# Elektriskeem.net
KiCad netlist of a schematic drawn in EAGLE
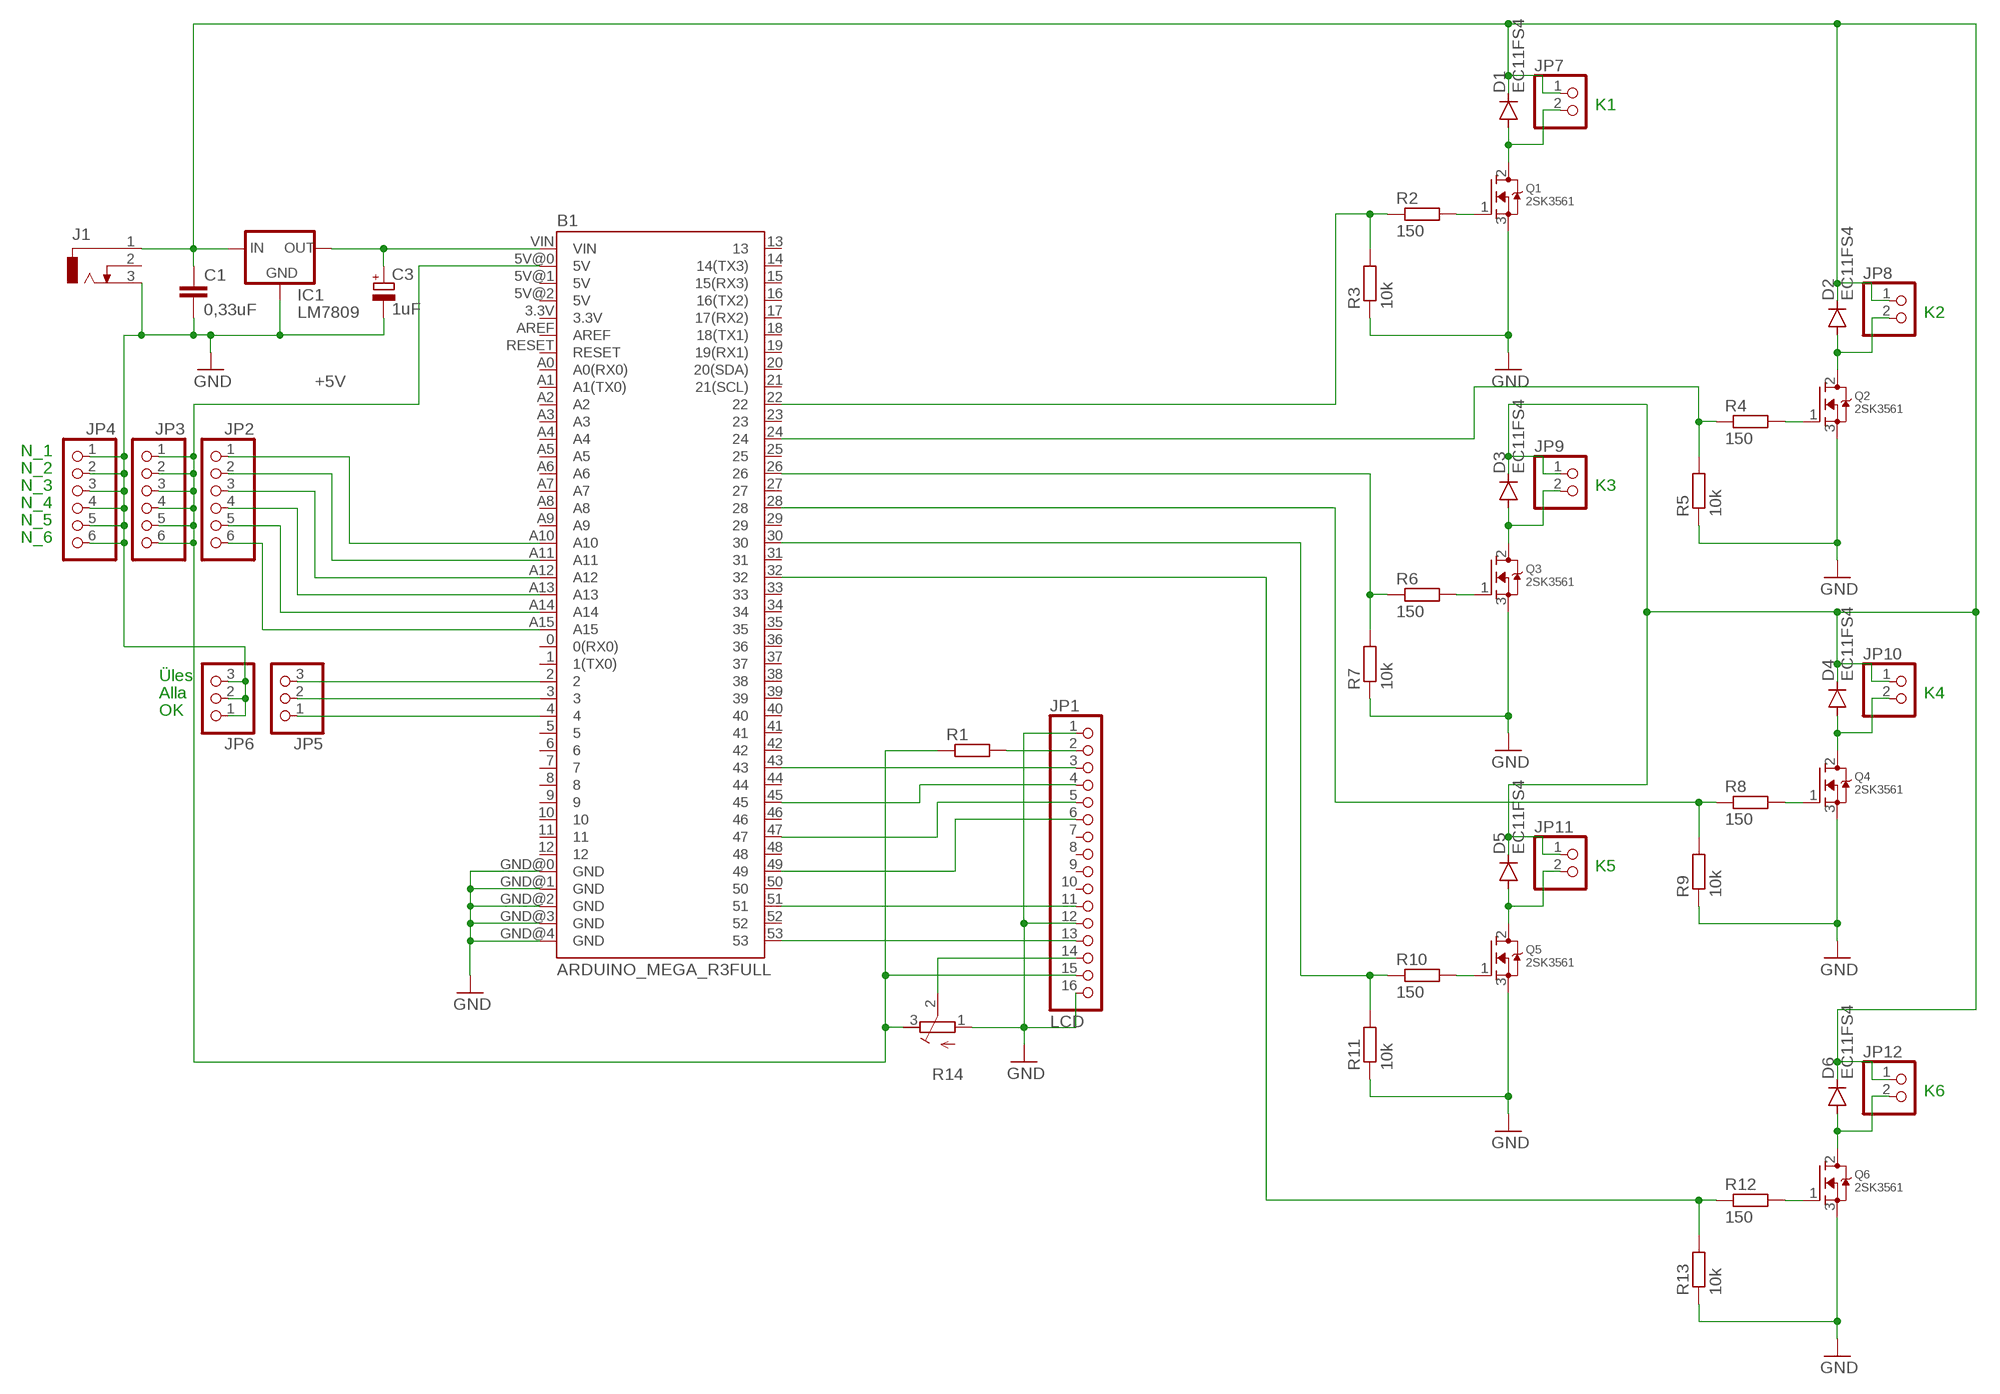
[diagram p0: schematic, sheet 1]

(export (version "E")
  (design (tool "Eeschema 10.0.6"))
  (components
    (comp (ref "B1")
      (value "ARDUINO_MEGA_R3FULL")
      (footprint "eagle-import:ARDUINO_MEGA")
      (libsource (lib "eagle-import") (part "ARDUINO_MEGA_R3FULL"))
    )
    (comp (ref "C1")
      (value "0,33uF")
      (footprint "eagle-import:C102-043X133")
      (libsource (lib "eagle-import") (part "C-EU102-043X133"))
    )
    (comp (ref "C3")
      (value "1uF")
      (footprint "eagle-import:E2,5-6")
      (libsource (lib "eagle-import") (part "CPOL-EUE2.5-6"))
    )
    (comp (ref "D1")
      (value "EC11FS4")
      (footprint "eagle-import:DO214AA")
      (libsource (lib "eagle-import") (part "DIODE-DO214AA"))
    )
    (comp (ref "D2")
      (value "EC11FS4")
      (footprint "eagle-import:DO214AA")
      (libsource (lib "eagle-import") (part "DIODE-DO214AA"))
    )
    (comp (ref "D3")
      (value "EC11FS4")
      (footprint "eagle-import:DO214AA")
      (libsource (lib "eagle-import") (part "DIODE-DO214AA"))
    )
    (comp (ref "D4")
      (value "EC11FS4")
      (footprint "eagle-import:DO214AA")
      (libsource (lib "eagle-import") (part "DIODE-DO214AA"))
    )
    (comp (ref "D5")
      (value "EC11FS4")
      (footprint "eagle-import:DO214AA")
      (libsource (lib "eagle-import") (part "DIODE-DO214AA"))
    )
    (comp (ref "D6")
      (value "EC11FS4")
      (footprint "eagle-import:DO214AA")
      (libsource (lib "eagle-import") (part "DIODE-DO214AA"))
    )
    (comp (ref "IC1")
      (value "LM7809")
      (footprint "eagle-import:78XXS")
      (libsource (lib "eagle-import") (part "78XXS"))
    )
    (comp (ref "J1")
      (value "DCJ0303")
      (footprint "eagle-import:DCJ0303")
      (libsource (lib "eagle-import") (part "DCJ0303"))
    )
    (comp (ref "JP1")
      (value "LCD")
      (footprint "eagle-import:1X16")
      (libsource (lib "eagle-import") (part "PINHD-1X16"))
    )
    (comp (ref "JP2")
      (value "PINHD-1X6")
      (footprint "eagle-import:1X06")
      (libsource (lib "eagle-import") (part "PINHD-1X6"))
    )
    (comp (ref "JP3")
      (value "PINHD-1X6")
      (footprint "eagle-import:1X06")
      (libsource (lib "eagle-import") (part "PINHD-1X6"))
    )
    (comp (ref "JP4")
      (value "PINHD-1X6")
      (footprint "eagle-import:1X06")
      (libsource (lib "eagle-import") (part "PINHD-1X6"))
    )
    (comp (ref "JP5")
      (value "PINHD-1X3")
      (footprint "eagle-import:1X03")
      (libsource (lib "eagle-import") (part "PINHD-1X3"))
    )
    (comp (ref "JP6")
      (value "PINHD-1X3")
      (footprint "eagle-import:1X03")
      (libsource (lib "eagle-import") (part "PINHD-1X3"))
    )
    (comp (ref "JP7")
      (value "PINHD-1X2")
      (footprint "eagle-import:1X02")
      (libsource (lib "eagle-import") (part "PINHD-1X2"))
    )
    (comp (ref "JP8")
      (value "PINHD-1X2")
      (footprint "eagle-import:1X02")
      (libsource (lib "eagle-import") (part "PINHD-1X2"))
    )
    (comp (ref "JP9")
      (value "PINHD-1X2")
      (footprint "eagle-import:1X02")
      (libsource (lib "eagle-import") (part "PINHD-1X2"))
    )
    (comp (ref "JP10")
      (value "PINHD-1X2")
      (footprint "eagle-import:1X02")
      (libsource (lib "eagle-import") (part "PINHD-1X2"))
    )
    (comp (ref "JP11")
      (value "PINHD-1X2")
      (footprint "eagle-import:1X02")
      (libsource (lib "eagle-import") (part "PINHD-1X2"))
    )
    (comp (ref "JP12")
      (value "PINHD-1X2")
      (footprint "eagle-import:1X02")
      (libsource (lib "eagle-import") (part "PINHD-1X2"))
    )
    (comp (ref "Q1")
      (value "2SK3561")
      (footprint "eagle-import:TO220V")
      (libsource (lib "eagle-import") (part "MOSFET-NGDS_TO220V"))
    )
    (comp (ref "Q2")
      (value "2SK3561")
      (footprint "eagle-import:TO220V")
      (libsource (lib "eagle-import") (part "MOSFET-NGDS_TO220V"))
    )
    (comp (ref "Q3")
      (value "2SK3561")
      (footprint "eagle-import:TO220V")
      (libsource (lib "eagle-import") (part "MOSFET-NGDS_TO220V"))
    )
    (comp (ref "Q4")
      (value "2SK3561")
      (footprint "eagle-import:TO220V")
      (libsource (lib "eagle-import") (part "MOSFET-NGDS_TO220V"))
    )
    (comp (ref "Q5")
      (value "2SK3561")
      (footprint "eagle-import:TO220V")
      (libsource (lib "eagle-import") (part "MOSFET-NGDS_TO220V"))
    )
    (comp (ref "Q6")
      (value "2SK3561")
      (footprint "eagle-import:TO220V")
      (libsource (lib "eagle-import") (part "MOSFET-NGDS_TO220V"))
    )
    (comp (ref "R1")
      (value "R-EU_0207/12")
      (footprint "eagle-import:0207_12")
      (libsource (lib "eagle-import") (part "R-EU_0207/12"))
    )
    (comp (ref "R2")
      (value "150")
      (footprint "eagle-import:0207_12")
      (libsource (lib "eagle-import") (part "R-EU_0207/12"))
    )
    (comp (ref "R3")
      (value "10k")
      (footprint "eagle-import:0207_12")
      (libsource (lib "eagle-import") (part "R-EU_0207/12"))
    )
    (comp (ref "R4")
      (value "150")
      (footprint "eagle-import:0207_12")
      (libsource (lib "eagle-import") (part "R-EU_0207/12"))
    )
    (comp (ref "R5")
      (value "10k")
      (footprint "eagle-import:0207_12")
      (libsource (lib "eagle-import") (part "R-EU_0207/12"))
    )
    (comp (ref "R6")
      (value "150")
      (footprint "eagle-import:0207_12")
      (libsource (lib "eagle-import") (part "R-EU_0207/12"))
    )
    (comp (ref "R7")
      (value "10k")
      (footprint "eagle-import:0207_12")
      (libsource (lib "eagle-import") (part "R-EU_0207/12"))
    )
    (comp (ref "R8")
      (value "150")
      (footprint "eagle-import:0207_12")
      (libsource (lib "eagle-import") (part "R-EU_0207/12"))
    )
    (comp (ref "R9")
      (value "10k")
      (footprint "eagle-import:0207_12")
      (libsource (lib "eagle-import") (part "R-EU_0207/12"))
    )
    (comp (ref "R10")
      (value "150")
      (footprint "eagle-import:0207_12")
      (libsource (lib "eagle-import") (part "R-EU_0207/12"))
    )
    (comp (ref "R11")
      (value "10k")
      (footprint "eagle-import:0207_12")
      (libsource (lib "eagle-import") (part "R-EU_0207/12"))
    )
    (comp (ref "R12")
      (value "150")
      (footprint "eagle-import:0207_12")
      (libsource (lib "eagle-import") (part "R-EU_0207/12"))
    )
    (comp (ref "R13")
      (value "10k")
      (footprint "eagle-import:0207_12")
      (libsource (lib "eagle-import") (part "R-EU_0207/12"))
    )
    (comp (ref "R14")
      (value "R-TRIMM3339P")
      (footprint "eagle-import:RTRIM3339P")
      (libsource (lib "eagle-import") (part "R-TRIMM3339P"))
    )
  )
  (nets
    (net (code "1") (name "/+5V") (class "Default")
      (node (ref "B1") (pin "5V@0") (pinfunction "5V_5V@0") (pintype "bidirectional"))
      (node (ref "JP1") (pin "15") (pinfunction "15_15") (pintype "passive"))
      (node (ref "JP3") (pin "1") (pinfunction "1_1") (pintype "passive"))
      (node (ref "JP3") (pin "2") (pinfunction "2_2") (pintype "passive"))
      (node (ref "JP3") (pin "3") (pinfunction "3_3") (pintype "passive"))
      (node (ref "JP3") (pin "4") (pinfunction "4_4") (pintype "passive"))
      (node (ref "JP3") (pin "5") (pinfunction "5_5") (pintype "passive"))
      (node (ref "JP3") (pin "6") (pinfunction "6_6") (pintype "passive"))
      (node (ref "R1") (pin "1") (pinfunction "1_1") (pintype "passive"))
      (node (ref "R14") (pin "3") (pinfunction "E_3") (pintype "passive"))
    )
    (net (code "2") (name "GND") (class "Default")
      (node (ref "B1") (pin "GND@0") (pinfunction "GND_GND@0") (pintype "bidirectional"))
      (node (ref "B1") (pin "GND@1") (pinfunction "GND_GND@1") (pintype "bidirectional"))
      (node (ref "B1") (pin "GND@2") (pinfunction "GND_GND@2") (pintype "bidirectional"))
      (node (ref "B1") (pin "GND@3") (pinfunction "GND_GND@3") (pintype "bidirectional"))
      (node (ref "B1") (pin "GND@4") (pinfunction "GND_GND@4") (pintype "bidirectional"))
      (node (ref "C1") (pin "2") (pinfunction "2_2") (pintype "passive"))
      (node (ref "C3") (pin "-") (pinfunction "-_-") (pintype "passive"))
      (node (ref "IC1") (pin "GND") (pinfunction "GND_GND") (pintype "input"))
      (node (ref "J1") (pin "3") (pinfunction "3_3") (pintype "passive"))
      (node (ref "JP1") (pin "1") (pinfunction "1_1") (pintype "passive"))
      (node (ref "JP1") (pin "12") (pinfunction "12_12") (pintype "passive"))
      (node (ref "JP1") (pin "16") (pinfunction "16_16") (pintype "passive"))
      (node (ref "JP4") (pin "1") (pinfunction "1_1") (pintype "passive"))
      (node (ref "JP4") (pin "2") (pinfunction "2_2") (pintype "passive"))
      (node (ref "JP4") (pin "3") (pinfunction "3_3") (pintype "passive"))
      (node (ref "JP4") (pin "4") (pinfunction "4_4") (pintype "passive"))
      (node (ref "JP4") (pin "5") (pinfunction "5_5") (pintype "passive"))
      (node (ref "JP4") (pin "6") (pinfunction "6_6") (pintype "passive"))
      (node (ref "JP6") (pin "1") (pinfunction "1_1") (pintype "passive"))
      (node (ref "JP6") (pin "2") (pinfunction "2_2") (pintype "passive"))
      (node (ref "JP6") (pin "3") (pinfunction "3_3") (pintype "passive"))
      (node (ref "Q1") (pin "3") (pinfunction "S_3") (pintype "bidirectional"))
      (node (ref "Q2") (pin "3") (pinfunction "S_3") (pintype "bidirectional"))
      (node (ref "Q3") (pin "3") (pinfunction "S_3") (pintype "bidirectional"))
      (node (ref "Q4") (pin "3") (pinfunction "S_3") (pintype "bidirectional"))
      (node (ref "Q5") (pin "3") (pinfunction "S_3") (pintype "bidirectional"))
      (node (ref "Q6") (pin "3") (pinfunction "S_3") (pintype "bidirectional"))
      (node (ref "R11") (pin "1") (pinfunction "1_1") (pintype "passive"))
      (node (ref "R13") (pin "1") (pinfunction "1_1") (pintype "passive"))
      (node (ref "R14") (pin "1") (pinfunction "A_1") (pintype "passive"))
      (node (ref "R3") (pin "1") (pinfunction "1_1") (pintype "passive"))
      (node (ref "R5") (pin "1") (pinfunction "1_1") (pintype "passive"))
      (node (ref "R7") (pin "1") (pinfunction "1_1") (pintype "passive"))
      (node (ref "R9") (pin "1") (pinfunction "1_1") (pintype "passive"))
    )
    (net (code "3") (name "Net-(B1-Pad2)") (class "Default")
      (node (ref "B1") (pin "2") (pinfunction "2_2") (pintype "bidirectional"))
      (node (ref "JP5") (pin "3") (pinfunction "3_3") (pintype "passive"))
    )
    (net (code "4") (name "Net-(B1-Pad3)") (class "Default")
      (node (ref "B1") (pin "3") (pinfunction "3_3") (pintype "bidirectional"))
      (node (ref "JP5") (pin "2") (pinfunction "2_2") (pintype "passive"))
    )
    (net (code "5") (name "Net-(B1-Pad4)") (class "Default")
      (node (ref "B1") (pin "4") (pinfunction "4_4") (pintype "bidirectional"))
      (node (ref "JP5") (pin "1") (pinfunction "1_1") (pintype "passive"))
    )
    (net (code "6") (name "Net-(B1-Pad22)") (class "Default")
      (node (ref "B1") (pin "22") (pinfunction "22_22") (pintype "bidirectional"))
      (node (ref "R2") (pin "1") (pinfunction "1_1") (pintype "passive"))
      (node (ref "R3") (pin "2") (pinfunction "2_2") (pintype "passive"))
    )
    (net (code "7") (name "Net-(B1-Pad24)") (class "Default")
      (node (ref "B1") (pin "24") (pinfunction "24_24") (pintype "bidirectional"))
      (node (ref "R4") (pin "1") (pinfunction "1_1") (pintype "passive"))
      (node (ref "R5") (pin "2") (pinfunction "2_2") (pintype "passive"))
    )
    (net (code "8") (name "Net-(B1-Pad26)") (class "Default")
      (node (ref "B1") (pin "26") (pinfunction "26_26") (pintype "bidirectional"))
      (node (ref "R6") (pin "1") (pinfunction "1_1") (pintype "passive"))
      (node (ref "R7") (pin "2") (pinfunction "2_2") (pintype "passive"))
    )
    (net (code "9") (name "Net-(B1-Pad28)") (class "Default")
      (node (ref "B1") (pin "28") (pinfunction "28_28") (pintype "bidirectional"))
      (node (ref "R8") (pin "1") (pinfunction "1_1") (pintype "passive"))
      (node (ref "R9") (pin "2") (pinfunction "2_2") (pintype "passive"))
    )
    (net (code "10") (name "Net-(B1-Pad30)") (class "Default")
      (node (ref "B1") (pin "30") (pinfunction "30_30") (pintype "bidirectional"))
      (node (ref "R10") (pin "1") (pinfunction "1_1") (pintype "passive"))
      (node (ref "R11") (pin "2") (pinfunction "2_2") (pintype "passive"))
    )
    (net (code "11") (name "Net-(B1-Pad32)") (class "Default")
      (node (ref "B1") (pin "32") (pinfunction "32_32") (pintype "bidirectional"))
      (node (ref "R12") (pin "1") (pinfunction "1_1") (pintype "passive"))
      (node (ref "R13") (pin "2") (pinfunction "2_2") (pintype "passive"))
    )
    (net (code "12") (name "Net-(B1-Pad43)") (class "Default")
      (node (ref "B1") (pin "43") (pinfunction "43_43") (pintype "bidirectional"))
      (node (ref "JP1") (pin "3") (pinfunction "3_3") (pintype "passive"))
    )
    (net (code "13") (name "Net-(B1-Pad45)") (class "Default")
      (node (ref "B1") (pin "45") (pinfunction "45_45") (pintype "bidirectional"))
      (node (ref "JP1") (pin "4") (pinfunction "4_4") (pintype "passive"))
    )
    (net (code "14") (name "Net-(B1-Pad47)") (class "Default")
      (node (ref "B1") (pin "47") (pinfunction "47_47") (pintype "bidirectional"))
      (node (ref "JP1") (pin "5") (pinfunction "5_5") (pintype "passive"))
    )
    (net (code "15") (name "Net-(B1-Pad49)") (class "Default")
      (node (ref "B1") (pin "49") (pinfunction "49_49") (pintype "bidirectional"))
      (node (ref "JP1") (pin "6") (pinfunction "6_6") (pintype "passive"))
    )
    (net (code "16") (name "Net-(B1-Pad51)") (class "Default")
      (node (ref "B1") (pin "51") (pinfunction "51_51") (pintype "bidirectional"))
      (node (ref "JP1") (pin "11") (pinfunction "11_11") (pintype "passive"))
    )
    (net (code "17") (name "Net-(B1-Pad53)") (class "Default")
      (node (ref "B1") (pin "53") (pinfunction "53_53") (pintype "bidirectional"))
      (node (ref "JP1") (pin "13") (pinfunction "13_13") (pintype "passive"))
    )
    (net (code "18") (name "Net-(B1-PadA10)") (class "Default")
      (node (ref "B1") (pin "A10") (pinfunction "A10_A10") (pintype "bidirectional"))
      (node (ref "JP2") (pin "1") (pinfunction "1_1") (pintype "passive"))
    )
    (net (code "19") (name "Net-(B1-PadA11)") (class "Default")
      (node (ref "B1") (pin "A11") (pinfunction "A11_A11") (pintype "bidirectional"))
      (node (ref "JP2") (pin "2") (pinfunction "2_2") (pintype "passive"))
    )
    (net (code "20") (name "Net-(B1-PadA12)") (class "Default")
      (node (ref "B1") (pin "A12") (pinfunction "A12_A12") (pintype "bidirectional"))
      (node (ref "JP2") (pin "3") (pinfunction "3_3") (pintype "passive"))
    )
    (net (code "21") (name "Net-(B1-PadA13)") (class "Default")
      (node (ref "B1") (pin "A13") (pinfunction "A13_A13") (pintype "bidirectional"))
      (node (ref "JP2") (pin "4") (pinfunction "4_4") (pintype "passive"))
    )
    (net (code "22") (name "Net-(B1-PadA14)") (class "Default")
      (node (ref "B1") (pin "A14") (pinfunction "A14_A14") (pintype "bidirectional"))
      (node (ref "JP2") (pin "5") (pinfunction "5_5") (pintype "passive"))
    )
    (net (code "23") (name "Net-(B1-PadA15)") (class "Default")
      (node (ref "B1") (pin "A15") (pinfunction "A15_A15") (pintype "bidirectional"))
      (node (ref "JP2") (pin "6") (pinfunction "6_6") (pintype "passive"))
    )
    (net (code "24") (name "Net-(B1-PadVIN)") (class "Default")
      (node (ref "B1") (pin "VIN") (pinfunction "VIN_VIN") (pintype "bidirectional"))
      (node (ref "C3") (pin "+") (pinfunction "+_+") (pintype "passive"))
      (node (ref "IC1") (pin "OUT") (pinfunction "OUT_OUT") (pintype "passive"))
    )
    (net (code "25") (name "Net-(C1-Pad1)") (class "Default")
      (node (ref "C1") (pin "1") (pinfunction "1_1") (pintype "passive"))
      (node (ref "D1") (pin "C") (pinfunction "C_C") (pintype "passive"))
      (node (ref "D2") (pin "C") (pinfunction "C_C") (pintype "passive"))
      (node (ref "D3") (pin "C") (pinfunction "C_C") (pintype "passive"))
      (node (ref "D4") (pin "C") (pinfunction "C_C") (pintype "passive"))
      (node (ref "D5") (pin "C") (pinfunction "C_C") (pintype "passive"))
      (node (ref "D6") (pin "C") (pinfunction "C_C") (pintype "passive"))
      (node (ref "IC1") (pin "IN") (pinfunction "IN_IN") (pintype "input"))
      (node (ref "J1") (pin "1") (pinfunction "1_1") (pintype "passive"))
      (node (ref "JP10") (pin "1") (pinfunction "1_1") (pintype "passive"))
      (node (ref "JP11") (pin "1") (pinfunction "1_1") (pintype "passive"))
      (node (ref "JP12") (pin "1") (pinfunction "1_1") (pintype "passive"))
      (node (ref "JP7") (pin "1") (pinfunction "1_1") (pintype "passive"))
      (node (ref "JP8") (pin "1") (pinfunction "1_1") (pintype "passive"))
      (node (ref "JP9") (pin "1") (pinfunction "1_1") (pintype "passive"))
    )
    (net (code "26") (name "Net-(JP1-Pad2)") (class "Default")
      (node (ref "JP1") (pin "2") (pinfunction "2_2") (pintype "passive"))
      (node (ref "R1") (pin "2") (pinfunction "2_2") (pintype "passive"))
    )
    (net (code "27") (name "Net-(Q1-D)") (class "Default")
      (node (ref "D1") (pin "A") (pinfunction "A_A") (pintype "passive"))
      (node (ref "JP7") (pin "2") (pinfunction "2_2") (pintype "passive"))
      (node (ref "Q1") (pin "2") (pinfunction "D_2") (pintype "bidirectional"))
    )
    (net (code "28") (name "Net-(Q1-G)") (class "Default")
      (node (ref "Q1") (pin "1") (pinfunction "G_1") (pintype "bidirectional"))
      (node (ref "R2") (pin "2") (pinfunction "2_2") (pintype "passive"))
    )
    (net (code "29") (name "Net-(Q2-D)") (class "Default")
      (node (ref "D2") (pin "A") (pinfunction "A_A") (pintype "passive"))
      (node (ref "JP8") (pin "2") (pinfunction "2_2") (pintype "passive"))
      (node (ref "Q2") (pin "2") (pinfunction "D_2") (pintype "bidirectional"))
    )
    (net (code "30") (name "Net-(Q2-G)") (class "Default")
      (node (ref "Q2") (pin "1") (pinfunction "G_1") (pintype "bidirectional"))
      (node (ref "R4") (pin "2") (pinfunction "2_2") (pintype "passive"))
    )
    (net (code "31") (name "Net-(Q3-D)") (class "Default")
      (node (ref "D3") (pin "A") (pinfunction "A_A") (pintype "passive"))
      (node (ref "JP9") (pin "2") (pinfunction "2_2") (pintype "passive"))
      (node (ref "Q3") (pin "2") (pinfunction "D_2") (pintype "bidirectional"))
    )
    (net (code "32") (name "Net-(Q3-G)") (class "Default")
      (node (ref "Q3") (pin "1") (pinfunction "G_1") (pintype "bidirectional"))
      (node (ref "R6") (pin "2") (pinfunction "2_2") (pintype "passive"))
    )
    (net (code "33") (name "Net-(Q4-D)") (class "Default")
      (node (ref "D4") (pin "A") (pinfunction "A_A") (pintype "passive"))
      (node (ref "JP10") (pin "2") (pinfunction "2_2") (pintype "passive"))
      (node (ref "Q4") (pin "2") (pinfunction "D_2") (pintype "bidirectional"))
    )
    (net (code "34") (name "Net-(Q4-G)") (class "Default")
      (node (ref "Q4") (pin "1") (pinfunction "G_1") (pintype "bidirectional"))
      (node (ref "R8") (pin "2") (pinfunction "2_2") (pintype "passive"))
    )
    (net (code "35") (name "Net-(Q5-D)") (class "Default")
      (node (ref "D5") (pin "A") (pinfunction "A_A") (pintype "passive"))
      (node (ref "JP11") (pin "2") (pinfunction "2_2") (pintype "passive"))
      (node (ref "Q5") (pin "2") (pinfunction "D_2") (pintype "bidirectional"))
    )
    (net (code "36") (name "Net-(Q5-G)") (class "Default")
      (node (ref "Q5") (pin "1") (pinfunction "G_1") (pintype "bidirectional"))
      (node (ref "R10") (pin "2") (pinfunction "2_2") (pintype "passive"))
    )
    (net (code "37") (name "Net-(Q6-D)") (class "Default")
      (node (ref "D6") (pin "A") (pinfunction "A_A") (pintype "passive"))
      (node (ref "JP12") (pin "2") (pinfunction "2_2") (pintype "passive"))
      (node (ref "Q6") (pin "2") (pinfunction "D_2") (pintype "bidirectional"))
    )
    (net (code "38") (name "Net-(Q6-G)") (class "Default")
      (node (ref "Q6") (pin "1") (pinfunction "G_1") (pintype "bidirectional"))
      (node (ref "R12") (pin "2") (pinfunction "2_2") (pintype "passive"))
    )
    (net (code "39") (name "Net-(R14-S)") (class "Default")
      (node (ref "JP1") (pin "14") (pinfunction "14_14") (pintype "passive"))
      (node (ref "R14") (pin "2") (pinfunction "S_2") (pintype "passive"))
    )
    (net (code "40") (name "unconnected-(B1-0(RX0)-Pad0)") (class "Default")
      (node (ref "B1") (pin "0") (pinfunction "0(RX0)_0") (pintype "bidirectional"))
    )
    (net (code "41") (name "unconnected-(B1-1(TX0)-Pad1)") (class "Default")
      (node (ref "B1") (pin "1") (pinfunction "1(TX0)_1") (pintype "bidirectional"))
    )
    (net (code "42") (name "unconnected-(B1-5V-Pad5V@1)") (class "Default")
      (node (ref "B1") (pin "5V@1") (pinfunction "5V_5V@1") (pintype "bidirectional"))
    )
    (net (code "43") (name "unconnected-(B1-5V-Pad5V@2)") (class "Default")
      (node (ref "B1") (pin "5V@2") (pinfunction "5V_5V@2") (pintype "bidirectional"))
    )
    (net (code "44") (name "unconnected-(B1-14(TX3)-Pad14)") (class "Default")
      (node (ref "B1") (pin "14") (pinfunction "14(TX3)_14") (pintype "bidirectional"))
    )
    (net (code "45") (name "unconnected-(B1-15(RX3)-Pad15)") (class "Default")
      (node (ref "B1") (pin "15") (pinfunction "15(RX3)_15") (pintype "bidirectional"))
    )
    (net (code "46") (name "unconnected-(B1-16(TX2)-Pad16)") (class "Default")
      (node (ref "B1") (pin "16") (pinfunction "16(TX2)_16") (pintype "bidirectional"))
    )
    (net (code "47") (name "unconnected-(B1-17(RX2)-Pad17)") (class "Default")
      (node (ref "B1") (pin "17") (pinfunction "17(RX2)_17") (pintype "bidirectional"))
    )
    (net (code "48") (name "unconnected-(B1-18(TX1)-Pad18)") (class "Default")
      (node (ref "B1") (pin "18") (pinfunction "18(TX1)_18") (pintype "bidirectional"))
    )
    (net (code "49") (name "unconnected-(B1-19(RX1)-Pad19)") (class "Default")
      (node (ref "B1") (pin "19") (pinfunction "19(RX1)_19") (pintype "bidirectional"))
    )
    (net (code "50") (name "unconnected-(B1-20(SDA)-Pad20)") (class "Default")
      (node (ref "B1") (pin "20") (pinfunction "20(SDA)_20") (pintype "bidirectional"))
    )
    (net (code "51") (name "unconnected-(B1-21(SCL)-Pad21)") (class "Default")
      (node (ref "B1") (pin "21") (pinfunction "21(SCL)_21") (pintype "bidirectional"))
    )
    (net (code "52") (name "unconnected-(B1-A0(RX0)-PadA0)") (class "Default")
      (node (ref "B1") (pin "A0") (pinfunction "A0(RX0)_A0") (pintype "bidirectional"))
    )
    (net (code "53") (name "unconnected-(B1-A1(TX0)-PadA1)") (class "Default")
      (node (ref "B1") (pin "A1") (pinfunction "A1(TX0)_A1") (pintype "bidirectional"))
    )
    (net (code "54") (name "unconnected-(B1-Pad3.3V)") (class "Default")
      (node (ref "B1") (pin "3.3V") (pinfunction "3.3V_3.3V") (pintype "bidirectional"))
    )
    (net (code "55") (name "unconnected-(B1-Pad5)") (class "Default")
      (node (ref "B1") (pin "5") (pinfunction "5_5") (pintype "bidirectional"))
    )
    (net (code "56") (name "unconnected-(B1-Pad6)") (class "Default")
      (node (ref "B1") (pin "6") (pinfunction "6_6") (pintype "bidirectional"))
    )
    (net (code "57") (name "unconnected-(B1-Pad7)") (class "Default")
      (node (ref "B1") (pin "7") (pinfunction "7_7") (pintype "bidirectional"))
    )
    (net (code "58") (name "unconnected-(B1-Pad8)") (class "Default")
      (node (ref "B1") (pin "8") (pinfunction "8_8") (pintype "bidirectional"))
    )
    (net (code "59") (name "unconnected-(B1-Pad9)") (class "Default")
      (node (ref "B1") (pin "9") (pinfunction "9_9") (pintype "bidirectional"))
    )
    (net (code "60") (name "unconnected-(B1-Pad10)") (class "Default")
      (node (ref "B1") (pin "10") (pinfunction "10_10") (pintype "bidirectional"))
    )
    (net (code "61") (name "unconnected-(B1-Pad11)") (class "Default")
      (node (ref "B1") (pin "11") (pinfunction "11_11") (pintype "bidirectional"))
    )
    (net (code "62") (name "unconnected-(B1-Pad12)") (class "Default")
      (node (ref "B1") (pin "12") (pinfunction "12_12") (pintype "bidirectional"))
    )
    (net (code "63") (name "unconnected-(B1-Pad13)") (class "Default")
      (node (ref "B1") (pin "13") (pinfunction "13_13") (pintype "bidirectional"))
    )
    (net (code "64") (name "unconnected-(B1-Pad23)") (class "Default")
      (node (ref "B1") (pin "23") (pinfunction "23_23") (pintype "bidirectional"))
    )
    (net (code "65") (name "unconnected-(B1-Pad25)") (class "Default")
      (node (ref "B1") (pin "25") (pinfunction "25_25") (pintype "bidirectional"))
    )
    (net (code "66") (name "unconnected-(B1-Pad27)") (class "Default")
      (node (ref "B1") (pin "27") (pinfunction "27_27") (pintype "bidirectional"))
    )
    (net (code "67") (name "unconnected-(B1-Pad29)") (class "Default")
      (node (ref "B1") (pin "29") (pinfunction "29_29") (pintype "bidirectional"))
    )
    (net (code "68") (name "unconnected-(B1-Pad31)") (class "Default")
      (node (ref "B1") (pin "31") (pinfunction "31_31") (pintype "bidirectional"))
    )
    (net (code "69") (name "unconnected-(B1-Pad33)") (class "Default")
      (node (ref "B1") (pin "33") (pinfunction "33_33") (pintype "bidirectional"))
    )
    (net (code "70") (name "unconnected-(B1-Pad34)") (class "Default")
      (node (ref "B1") (pin "34") (pinfunction "34_34") (pintype "bidirectional"))
    )
    (net (code "71") (name "unconnected-(B1-Pad35)") (class "Default")
      (node (ref "B1") (pin "35") (pinfunction "35_35") (pintype "bidirectional"))
    )
    (net (code "72") (name "unconnected-(B1-Pad36)") (class "Default")
      (node (ref "B1") (pin "36") (pinfunction "36_36") (pintype "bidirectional"))
    )
    (net (code "73") (name "unconnected-(B1-Pad37)") (class "Default")
      (node (ref "B1") (pin "37") (pinfunction "37_37") (pintype "bidirectional"))
    )
    (net (code "74") (name "unconnected-(B1-Pad38)") (class "Default")
      (node (ref "B1") (pin "38") (pinfunction "38_38") (pintype "bidirectional"))
    )
    (net (code "75") (name "unconnected-(B1-Pad39)") (class "Default")
      (node (ref "B1") (pin "39") (pinfunction "39_39") (pintype "bidirectional"))
    )
    (net (code "76") (name "unconnected-(B1-Pad40)") (class "Default")
      (node (ref "B1") (pin "40") (pinfunction "40_40") (pintype "bidirectional"))
    )
    (net (code "77") (name "unconnected-(B1-Pad41)") (class "Default")
      (node (ref "B1") (pin "41") (pinfunction "41_41") (pintype "bidirectional"))
    )
    (net (code "78") (name "unconnected-(B1-Pad42)") (class "Default")
      (node (ref "B1") (pin "42") (pinfunction "42_42") (pintype "bidirectional"))
    )
    (net (code "79") (name "unconnected-(B1-Pad44)") (class "Default")
      (node (ref "B1") (pin "44") (pinfunction "44_44") (pintype "bidirectional"))
    )
    (net (code "80") (name "unconnected-(B1-Pad46)") (class "Default")
      (node (ref "B1") (pin "46") (pinfunction "46_46") (pintype "bidirectional"))
    )
    (net (code "81") (name "unconnected-(B1-Pad48)") (class "Default")
      (node (ref "B1") (pin "48") (pinfunction "48_48") (pintype "bidirectional"))
    )
    (net (code "82") (name "unconnected-(B1-Pad50)") (class "Default")
      (node (ref "B1") (pin "50") (pinfunction "50_50") (pintype "bidirectional"))
    )
    (net (code "83") (name "unconnected-(B1-Pad52)") (class "Default")
      (node (ref "B1") (pin "52") (pinfunction "52_52") (pintype "bidirectional"))
    )
    (net (code "84") (name "unconnected-(B1-PadA2)") (class "Default")
      (node (ref "B1") (pin "A2") (pinfunction "A2_A2") (pintype "bidirectional"))
    )
    (net (code "85") (name "unconnected-(B1-PadA3)") (class "Default")
      (node (ref "B1") (pin "A3") (pinfunction "A3_A3") (pintype "bidirectional"))
    )
    (net (code "86") (name "unconnected-(B1-PadA4)") (class "Default")
      (node (ref "B1") (pin "A4") (pinfunction "A4_A4") (pintype "bidirectional"))
    )
    (net (code "87") (name "unconnected-(B1-PadA5)") (class "Default")
      (node (ref "B1") (pin "A5") (pinfunction "A5_A5") (pintype "bidirectional"))
    )
    (net (code "88") (name "unconnected-(B1-PadA6)") (class "Default")
      (node (ref "B1") (pin "A6") (pinfunction "A6_A6") (pintype "bidirectional"))
    )
    (net (code "89") (name "unconnected-(B1-PadA7)") (class "Default")
      (node (ref "B1") (pin "A7") (pinfunction "A7_A7") (pintype "bidirectional"))
    )
    (net (code "90") (name "unconnected-(B1-PadA8)") (class "Default")
      (node (ref "B1") (pin "A8") (pinfunction "A8_A8") (pintype "bidirectional"))
    )
    (net (code "91") (name "unconnected-(B1-PadA9)") (class "Default")
      (node (ref "B1") (pin "A9") (pinfunction "A9_A9") (pintype "bidirectional"))
    )
    (net (code "92") (name "unconnected-(B1-PadAREF)") (class "Default")
      (node (ref "B1") (pin "AREF") (pinfunction "AREF_AREF") (pintype "bidirectional"))
    )
    (net (code "93") (name "unconnected-(B1-PadRESET)") (class "Default")
      (node (ref "B1") (pin "RESET") (pinfunction "RESET_RESET") (pintype "bidirectional"))
    )
    (net (code "94") (name "unconnected-(J1-Pad2)") (class "Default")
      (node (ref "J1") (pin "2") (pinfunction "2_2") (pintype "passive"))
    )
    (net (code "95") (name "unconnected-(JP1-Pad7)") (class "Default")
      (node (ref "JP1") (pin "7") (pinfunction "7_7") (pintype "passive"))
    )
    (net (code "96") (name "unconnected-(JP1-Pad8)") (class "Default")
      (node (ref "JP1") (pin "8") (pinfunction "8_8") (pintype "passive"))
    )
    (net (code "97") (name "unconnected-(JP1-Pad9)") (class "Default")
      (node (ref "JP1") (pin "9") (pinfunction "9_9") (pintype "passive"))
    )
    (net (code "98") (name "unconnected-(JP1-Pad10)") (class "Default")
      (node (ref "JP1") (pin "10") (pinfunction "10_10") (pintype "passive"))
    )
  )
)
